# minimumduino-lenoardo.net
KiCad netlist of a schematic drawn in EAGLE
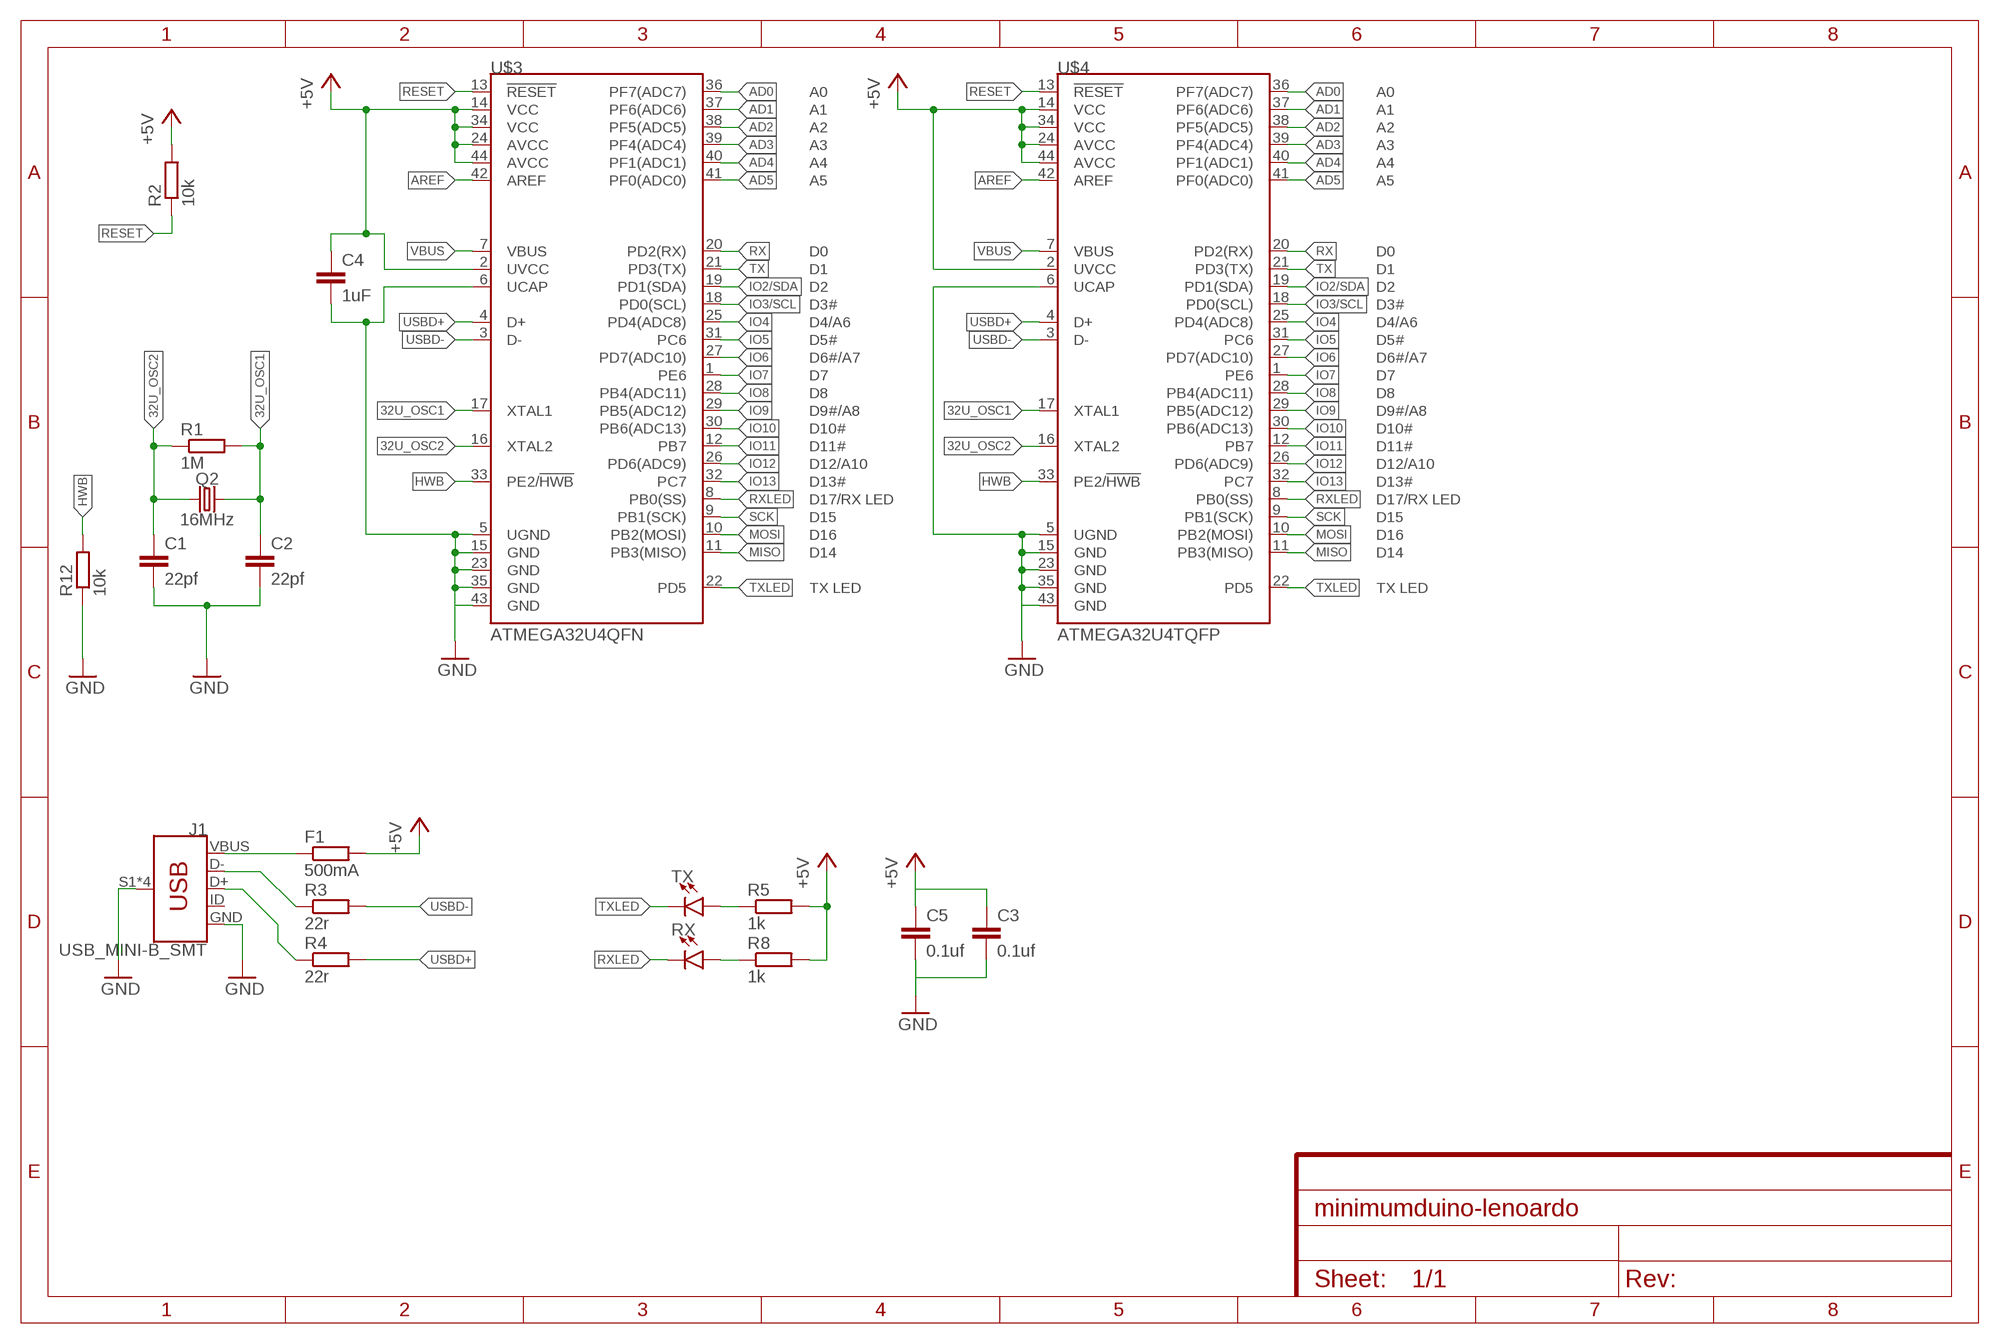
[diagram p0: schematic, sheet 1]

(export (version "E")
  (design (tool "Eeschema 10.0.6"))
  (components
    (comp (ref "C1")
      (value "22pf")
      (footprint "eagle-import:C0805")
      (libsource (lib "eagle-import") (part "C-EUC0805"))
    )
    (comp (ref "C2")
      (value "22pf")
      (footprint "eagle-import:C0805")
      (libsource (lib "eagle-import") (part "C-EUC0805"))
    )
    (comp (ref "C3")
      (value "0.1uf")
      (footprint "eagle-import:C0805")
      (libsource (lib "eagle-import") (part "C-EUC0805"))
    )
    (comp (ref "C4")
      (value "1uF")
      (footprint "eagle-import:C0805")
      (libsource (lib "eagle-import") (part "C-EUC0805"))
    )
    (comp (ref "C5")
      (value "0.1uf")
      (footprint "eagle-import:C0805")
      (libsource (lib "eagle-import") (part "C-EUC0805"))
    )
    (comp (ref "F1")
      (value "500mA")
      (footprint "eagle-import:R1206")
      (libsource (lib "eagle-import") (part "R-EU_R1206"))
    )
    (comp (ref "J1")
      (value "USB_MINI-B_SMT")
      (footprint "eagle-import:USB-MINIB")
      (libsource (lib "eagle-import") (part "USB_MINI-B_SMT"))
    )
    (comp (ref "Q2")
      (value "16MHz")
      (footprint "eagle-import:CRYSTAL-SMD-5X3.2-4PAD")
      (libsource (lib "eagle-import") (part "CRYSTAL-16MHZSMD-5X3.2"))
    )
    (comp (ref "R1")
      (value "1M")
      (footprint "eagle-import:R0805")
      (libsource (lib "eagle-import") (part "R-EU_R0805"))
    )
    (comp (ref "R2")
      (value "10k")
      (footprint "eagle-import:R0805")
      (libsource (lib "eagle-import") (part "R-EU_R0805"))
    )
    (comp (ref "R3")
      (value "22r")
      (footprint "eagle-import:R0805")
      (libsource (lib "eagle-import") (part "R-EU_R0805"))
    )
    (comp (ref "R4")
      (value "22r")
      (footprint "eagle-import:R0805")
      (libsource (lib "eagle-import") (part "R-EU_R0805"))
    )
    (comp (ref "R5")
      (value "1k")
      (footprint "eagle-import:R0805")
      (libsource (lib "eagle-import") (part "R-EU_R0805"))
    )
    (comp (ref "R8")
      (value "1k")
      (footprint "eagle-import:R0805")
      (libsource (lib "eagle-import") (part "R-EU_R0805"))
    )
    (comp (ref "R12")
      (value "10k")
      (footprint "eagle-import:R0805")
      (libsource (lib "eagle-import") (part "R-EU_R0805"))
    )
    (comp (ref "RX")
      (value "LED1206")
      (footprint "eagle-import:LED-1206")
      (libsource (lib "eagle-import") (part "LED1206"))
    )
    (comp (ref "TX")
      (value "LED1206")
      (footprint "eagle-import:LED-1206")
      (libsource (lib "eagle-import") (part "LED1206"))
    )
    (comp (ref "U$3")
      (value "ATMEGA32U4QFN")
      (footprint "eagle-import:SPARKFUN-DIGITALIC_QFN-44")
      (libsource (lib "eagle-import") (part "ATMEGA32U4QFN"))
    )
    (comp (ref "U$4")
      (value "ATMEGA32U4TQFP")
      (footprint "eagle-import:SPARKFUN-DIGITALIC_TQFP44")
      (libsource (lib "eagle-import") (part "ATMEGA32U4TQFP"))
    )
  )
  (nets
    (net (code "1") (name "+5V") (class "Default")
      (node (ref "C3") (pin "1") (pinfunction "1_1") (pintype "passive"))
      (node (ref "C4") (pin "1") (pinfunction "1_1") (pintype "passive"))
      (node (ref "C5") (pin "1") (pinfunction "1_1") (pintype "passive"))
      (node (ref "F1") (pin "2") (pinfunction "2_2") (pintype "passive"))
      (node (ref "R2") (pin "2") (pinfunction "2_2") (pintype "passive"))
      (node (ref "R5") (pin "2") (pinfunction "2_2") (pintype "passive"))
      (node (ref "R8") (pin "2") (pinfunction "2_2") (pintype "passive"))
      (node (ref "U$3") (pin "14") (pinfunction "VCC_14") (pintype "bidirectional"))
      (node (ref "U$3") (pin "2") (pinfunction "UVCC_2") (pintype "bidirectional"))
      (node (ref "U$3") (pin "24") (pinfunction "AVCC_24") (pintype "bidirectional"))
      (node (ref "U$3") (pin "34") (pinfunction "VCC_34") (pintype "bidirectional"))
      (node (ref "U$3") (pin "44") (pinfunction "AVCC_44") (pintype "bidirectional"))
      (node (ref "U$4") (pin "14") (pinfunction "VCC_14") (pintype "bidirectional"))
      (node (ref "U$4") (pin "2") (pinfunction "UVCC_2") (pintype "bidirectional"))
      (node (ref "U$4") (pin "24") (pinfunction "AVCC_24") (pintype "bidirectional"))
      (node (ref "U$4") (pin "34") (pinfunction "VCC_34") (pintype "bidirectional"))
      (node (ref "U$4") (pin "44") (pinfunction "AVCC_44") (pintype "bidirectional"))
    )
    (net (code "2") (name "32U_OSC1") (class "Default")
      (node (ref "C2") (pin "1") (pinfunction "1_1") (pintype "passive"))
      (node (ref "Q2") (pin "3") (pinfunction "2_3") (pintype "passive"))
      (node (ref "R1") (pin "2") (pinfunction "2_2") (pintype "passive"))
      (node (ref "U$3") (pin "17") (pinfunction "XTAL1_17") (pintype "bidirectional"))
      (node (ref "U$4") (pin "17") (pinfunction "XTAL1_17") (pintype "bidirectional"))
    )
    (net (code "3") (name "32U_OSC2") (class "Default")
      (node (ref "C1") (pin "1") (pinfunction "1_1") (pintype "passive"))
      (node (ref "Q2") (pin "1") (pinfunction "1_1") (pintype "passive"))
      (node (ref "R1") (pin "1") (pinfunction "1_1") (pintype "passive"))
      (node (ref "U$3") (pin "16") (pinfunction "XTAL2_16") (pintype "bidirectional"))
      (node (ref "U$4") (pin "16") (pinfunction "XTAL2_16") (pintype "bidirectional"))
    )
    (net (code "4") (name "AD0") (class "Default")
      (node (ref "U$3") (pin "36") (pinfunction "PF7(ADC7)_36") (pintype "bidirectional"))
      (node (ref "U$4") (pin "36") (pinfunction "PF7(ADC7)_36") (pintype "bidirectional"))
    )
    (net (code "5") (name "AD1") (class "Default")
      (node (ref "U$3") (pin "37") (pinfunction "PF6(ADC6)_37") (pintype "bidirectional"))
      (node (ref "U$4") (pin "37") (pinfunction "PF6(ADC6)_37") (pintype "bidirectional"))
    )
    (net (code "6") (name "AD2") (class "Default")
      (node (ref "U$3") (pin "38") (pinfunction "PF5(ADC5)_38") (pintype "bidirectional"))
      (node (ref "U$4") (pin "38") (pinfunction "PF5(ADC5)_38") (pintype "bidirectional"))
    )
    (net (code "7") (name "AD3") (class "Default")
      (node (ref "U$3") (pin "39") (pinfunction "PF4(ADC4)_39") (pintype "bidirectional"))
      (node (ref "U$4") (pin "39") (pinfunction "PF4(ADC4)_39") (pintype "bidirectional"))
    )
    (net (code "8") (name "AD4") (class "Default")
      (node (ref "U$3") (pin "40") (pinfunction "PF1(ADC1)_40") (pintype "bidirectional"))
      (node (ref "U$4") (pin "40") (pinfunction "PF1(ADC1)_40") (pintype "bidirectional"))
    )
    (net (code "9") (name "AD5") (class "Default")
      (node (ref "U$3") (pin "41") (pinfunction "PF0(ADC0)_41") (pintype "bidirectional"))
      (node (ref "U$4") (pin "41") (pinfunction "PF0(ADC0)_41") (pintype "bidirectional"))
    )
    (net (code "10") (name "AREF") (class "Default")
      (node (ref "U$3") (pin "42") (pinfunction "AREF_42") (pintype "bidirectional"))
      (node (ref "U$4") (pin "42") (pinfunction "AREF_42") (pintype "bidirectional"))
    )
    (net (code "11") (name "GND") (class "Default")
      (node (ref "C1") (pin "2") (pinfunction "2_2") (pintype "passive"))
      (node (ref "C2") (pin "2") (pinfunction "2_2") (pintype "passive"))
      (node (ref "C3") (pin "2") (pinfunction "2_2") (pintype "passive"))
      (node (ref "C4") (pin "2") (pinfunction "2_2") (pintype "passive"))
      (node (ref "C5") (pin "2") (pinfunction "2_2") (pintype "passive"))
      (node (ref "J1") (pin "GND") (pinfunction "GND_GND") (pintype "power_in"))
      (node (ref "J1") (pin "S1") (pinfunction "SHIELD_S1") (pintype "bidirectional"))
      (node (ref "J1") (pin "S2") (pinfunction "SHIELD_S2") (pintype "bidirectional"))
      (node (ref "J1") (pin "S3") (pinfunction "SHIELD_S3") (pintype "bidirectional"))
      (node (ref "J1") (pin "S4") (pinfunction "SHIELD_S4") (pintype "bidirectional"))
      (node (ref "R12") (pin "1") (pinfunction "1_1") (pintype "passive"))
      (node (ref "U$3") (pin "15") (pinfunction "GND_15") (pintype "bidirectional"))
      (node (ref "U$3") (pin "23") (pinfunction "GND_23") (pintype "bidirectional"))
      (node (ref "U$3") (pin "35") (pinfunction "GND_35") (pintype "bidirectional"))
      (node (ref "U$3") (pin "43") (pinfunction "GND_43") (pintype "bidirectional"))
      (node (ref "U$3") (pin "5") (pinfunction "UGND_5") (pintype "bidirectional"))
      (node (ref "U$3") (pin "6") (pinfunction "UCAP_6") (pintype "bidirectional"))
      (node (ref "U$4") (pin "15") (pinfunction "GND_15") (pintype "bidirectional"))
      (node (ref "U$4") (pin "23") (pinfunction "GND_23") (pintype "bidirectional"))
      (node (ref "U$4") (pin "35") (pinfunction "GND_35") (pintype "bidirectional"))
      (node (ref "U$4") (pin "43") (pinfunction "GND_43") (pintype "bidirectional"))
      (node (ref "U$4") (pin "5") (pinfunction "UGND_5") (pintype "bidirectional"))
      (node (ref "U$4") (pin "6") (pinfunction "UCAP_6") (pintype "bidirectional"))
    )
    (net (code "12") (name "HWB") (class "Default")
      (node (ref "R12") (pin "2") (pinfunction "2_2") (pintype "passive"))
      (node (ref "U$3") (pin "33") (pinfunction "PE2/~{HWB}_33") (pintype "bidirectional"))
      (node (ref "U$4") (pin "33") (pinfunction "PE2/~{HWB}_33") (pintype "bidirectional"))
    )
    (net (code "13") (name "IO2{slash}SDA") (class "Default")
      (node (ref "U$3") (pin "19") (pinfunction "PD1(SDA)_19") (pintype "bidirectional"))
      (node (ref "U$4") (pin "19") (pinfunction "PD1(SDA)_19") (pintype "bidirectional"))
    )
    (net (code "14") (name "IO3{slash}SCL") (class "Default")
      (node (ref "U$3") (pin "18") (pinfunction "PD0(SCL)_18") (pintype "bidirectional"))
      (node (ref "U$4") (pin "18") (pinfunction "PD0(SCL)_18") (pintype "bidirectional"))
    )
    (net (code "15") (name "IO4") (class "Default")
      (node (ref "U$3") (pin "25") (pinfunction "PD4(ADC8)_25") (pintype "bidirectional"))
      (node (ref "U$4") (pin "25") (pinfunction "PD4(ADC8)_25") (pintype "bidirectional"))
    )
    (net (code "16") (name "IO5") (class "Default")
      (node (ref "U$3") (pin "31") (pinfunction "PC6_31") (pintype "bidirectional"))
      (node (ref "U$4") (pin "31") (pinfunction "PC6_31") (pintype "bidirectional"))
    )
    (net (code "17") (name "IO6") (class "Default")
      (node (ref "U$3") (pin "27") (pinfunction "PD7(ADC10)_27") (pintype "bidirectional"))
      (node (ref "U$4") (pin "27") (pinfunction "PD7(ADC10)_27") (pintype "bidirectional"))
    )
    (net (code "18") (name "IO7") (class "Default")
      (node (ref "U$3") (pin "1") (pinfunction "PE6_1") (pintype "bidirectional"))
      (node (ref "U$4") (pin "1") (pinfunction "PE6_1") (pintype "bidirectional"))
    )
    (net (code "19") (name "IO8") (class "Default")
      (node (ref "U$3") (pin "28") (pinfunction "PB4(ADC11)_28") (pintype "bidirectional"))
      (node (ref "U$4") (pin "28") (pinfunction "PB4(ADC11)_28") (pintype "bidirectional"))
    )
    (net (code "20") (name "IO9") (class "Default")
      (node (ref "U$3") (pin "29") (pinfunction "PB5(ADC12)_29") (pintype "bidirectional"))
      (node (ref "U$4") (pin "29") (pinfunction "PB5(ADC12)_29") (pintype "bidirectional"))
    )
    (net (code "21") (name "IO10") (class "Default")
      (node (ref "U$3") (pin "30") (pinfunction "PB6(ADC13)_30") (pintype "bidirectional"))
      (node (ref "U$4") (pin "30") (pinfunction "PB6(ADC13)_30") (pintype "bidirectional"))
    )
    (net (code "22") (name "IO11") (class "Default")
      (node (ref "U$3") (pin "12") (pinfunction "PB7_12") (pintype "bidirectional"))
      (node (ref "U$4") (pin "12") (pinfunction "PB7_12") (pintype "bidirectional"))
    )
    (net (code "23") (name "IO12") (class "Default")
      (node (ref "U$3") (pin "26") (pinfunction "PD6(ADC9)_26") (pintype "bidirectional"))
      (node (ref "U$4") (pin "26") (pinfunction "PD6(ADC9)_26") (pintype "bidirectional"))
    )
    (net (code "24") (name "IO13") (class "Default")
      (node (ref "U$3") (pin "32") (pinfunction "PC7_32") (pintype "bidirectional"))
      (node (ref "U$4") (pin "32") (pinfunction "PC7_32") (pintype "bidirectional"))
    )
    (net (code "25") (name "MISO") (class "Default")
      (node (ref "U$3") (pin "11") (pinfunction "PB3(MISO)_11") (pintype "bidirectional"))
      (node (ref "U$4") (pin "11") (pinfunction "PB3(MISO)_11") (pintype "bidirectional"))
    )
    (net (code "26") (name "MOSI") (class "Default")
      (node (ref "U$3") (pin "10") (pinfunction "PB2(MOSI)_10") (pintype "bidirectional"))
      (node (ref "U$4") (pin "10") (pinfunction "PB2(MOSI)_10") (pintype "bidirectional"))
    )
    (net (code "27") (name "Net-(F1-Pad1)") (class "Default")
      (node (ref "F1") (pin "1") (pinfunction "1_1") (pintype "passive"))
      (node (ref "J1") (pin "VBUS") (pinfunction "VBUS_VBUS") (pintype "power_in"))
    )
    (net (code "28") (name "Net-(J1-PadD+)") (class "Default")
      (node (ref "J1") (pin "D+") (pinfunction "D+_D+") (pintype "bidirectional"))
      (node (ref "R4") (pin "1") (pinfunction "1_1") (pintype "passive"))
    )
    (net (code "29") (name "Net-(J1-PadD-)") (class "Default")
      (node (ref "J1") (pin "D-") (pinfunction "D-_D-") (pintype "bidirectional"))
      (node (ref "R3") (pin "1") (pinfunction "1_1") (pintype "passive"))
    )
    (net (code "30") (name "Net-(R5-Pad1)") (class "Default")
      (node (ref "R5") (pin "1") (pinfunction "1_1") (pintype "passive"))
      (node (ref "TX") (pin "A") (pinfunction "A_A") (pintype "passive"))
    )
    (net (code "31") (name "Net-(R8-Pad1)") (class "Default")
      (node (ref "R8") (pin "1") (pinfunction "1_1") (pintype "passive"))
      (node (ref "RX") (pin "A") (pinfunction "A_A") (pintype "passive"))
    )
    (net (code "32") (name "RESET") (class "Default")
      (node (ref "R2") (pin "1") (pinfunction "1_1") (pintype "passive"))
      (node (ref "U$3") (pin "13") (pinfunction "~{RESET}_13") (pintype "bidirectional"))
      (node (ref "U$4") (pin "13") (pinfunction "~{RESET}_13") (pintype "bidirectional"))
    )
    (net (code "33") (name "RX") (class "Default")
      (node (ref "U$3") (pin "20") (pinfunction "PD2(RX)_20") (pintype "bidirectional"))
      (node (ref "U$4") (pin "20") (pinfunction "PD2(RX)_20") (pintype "bidirectional"))
    )
    (net (code "34") (name "RXLED") (class "Default")
      (node (ref "RX") (pin "C") (pinfunction "C_C") (pintype "passive"))
      (node (ref "U$3") (pin "8") (pinfunction "PB0(SS)_8") (pintype "bidirectional"))
      (node (ref "U$4") (pin "8") (pinfunction "PB0(SS)_8") (pintype "bidirectional"))
    )
    (net (code "35") (name "SCK") (class "Default")
      (node (ref "U$3") (pin "9") (pinfunction "PB1(SCK)_9") (pintype "bidirectional"))
      (node (ref "U$4") (pin "9") (pinfunction "PB1(SCK)_9") (pintype "bidirectional"))
    )
    (net (code "36") (name "TX") (class "Default")
      (node (ref "U$3") (pin "21") (pinfunction "PD3(TX)_21") (pintype "bidirectional"))
      (node (ref "U$4") (pin "21") (pinfunction "PD3(TX)_21") (pintype "bidirectional"))
    )
    (net (code "37") (name "TXLED") (class "Default")
      (node (ref "TX") (pin "C") (pinfunction "C_C") (pintype "passive"))
      (node (ref "U$3") (pin "22") (pinfunction "PD5_22") (pintype "bidirectional"))
      (node (ref "U$4") (pin "22") (pinfunction "PD5_22") (pintype "bidirectional"))
    )
    (net (code "38") (name "USBD+") (class "Default")
      (node (ref "R4") (pin "2") (pinfunction "2_2") (pintype "passive"))
      (node (ref "U$3") (pin "4") (pinfunction "D+_4") (pintype "bidirectional"))
      (node (ref "U$4") (pin "4") (pinfunction "D+_4") (pintype "bidirectional"))
    )
    (net (code "39") (name "USBD-") (class "Default")
      (node (ref "R3") (pin "2") (pinfunction "2_2") (pintype "passive"))
      (node (ref "U$3") (pin "3") (pinfunction "D-_3") (pintype "bidirectional"))
      (node (ref "U$4") (pin "3") (pinfunction "D-_3") (pintype "bidirectional"))
    )
    (net (code "40") (name "VBUS") (class "Default")
      (node (ref "U$3") (pin "7") (pinfunction "VBUS_7") (pintype "bidirectional"))
      (node (ref "U$4") (pin "7") (pinfunction "VBUS_7") (pintype "bidirectional"))
    )
    (net (code "41") (name "unconnected-(J1-PadID)") (class "Default")
      (node (ref "J1") (pin "ID") (pinfunction "ID_ID") (pintype "bidirectional"))
    )
  )
)
